# HW_V4_1.net
KiCad netlist of a schematic drawn in Altium Designer
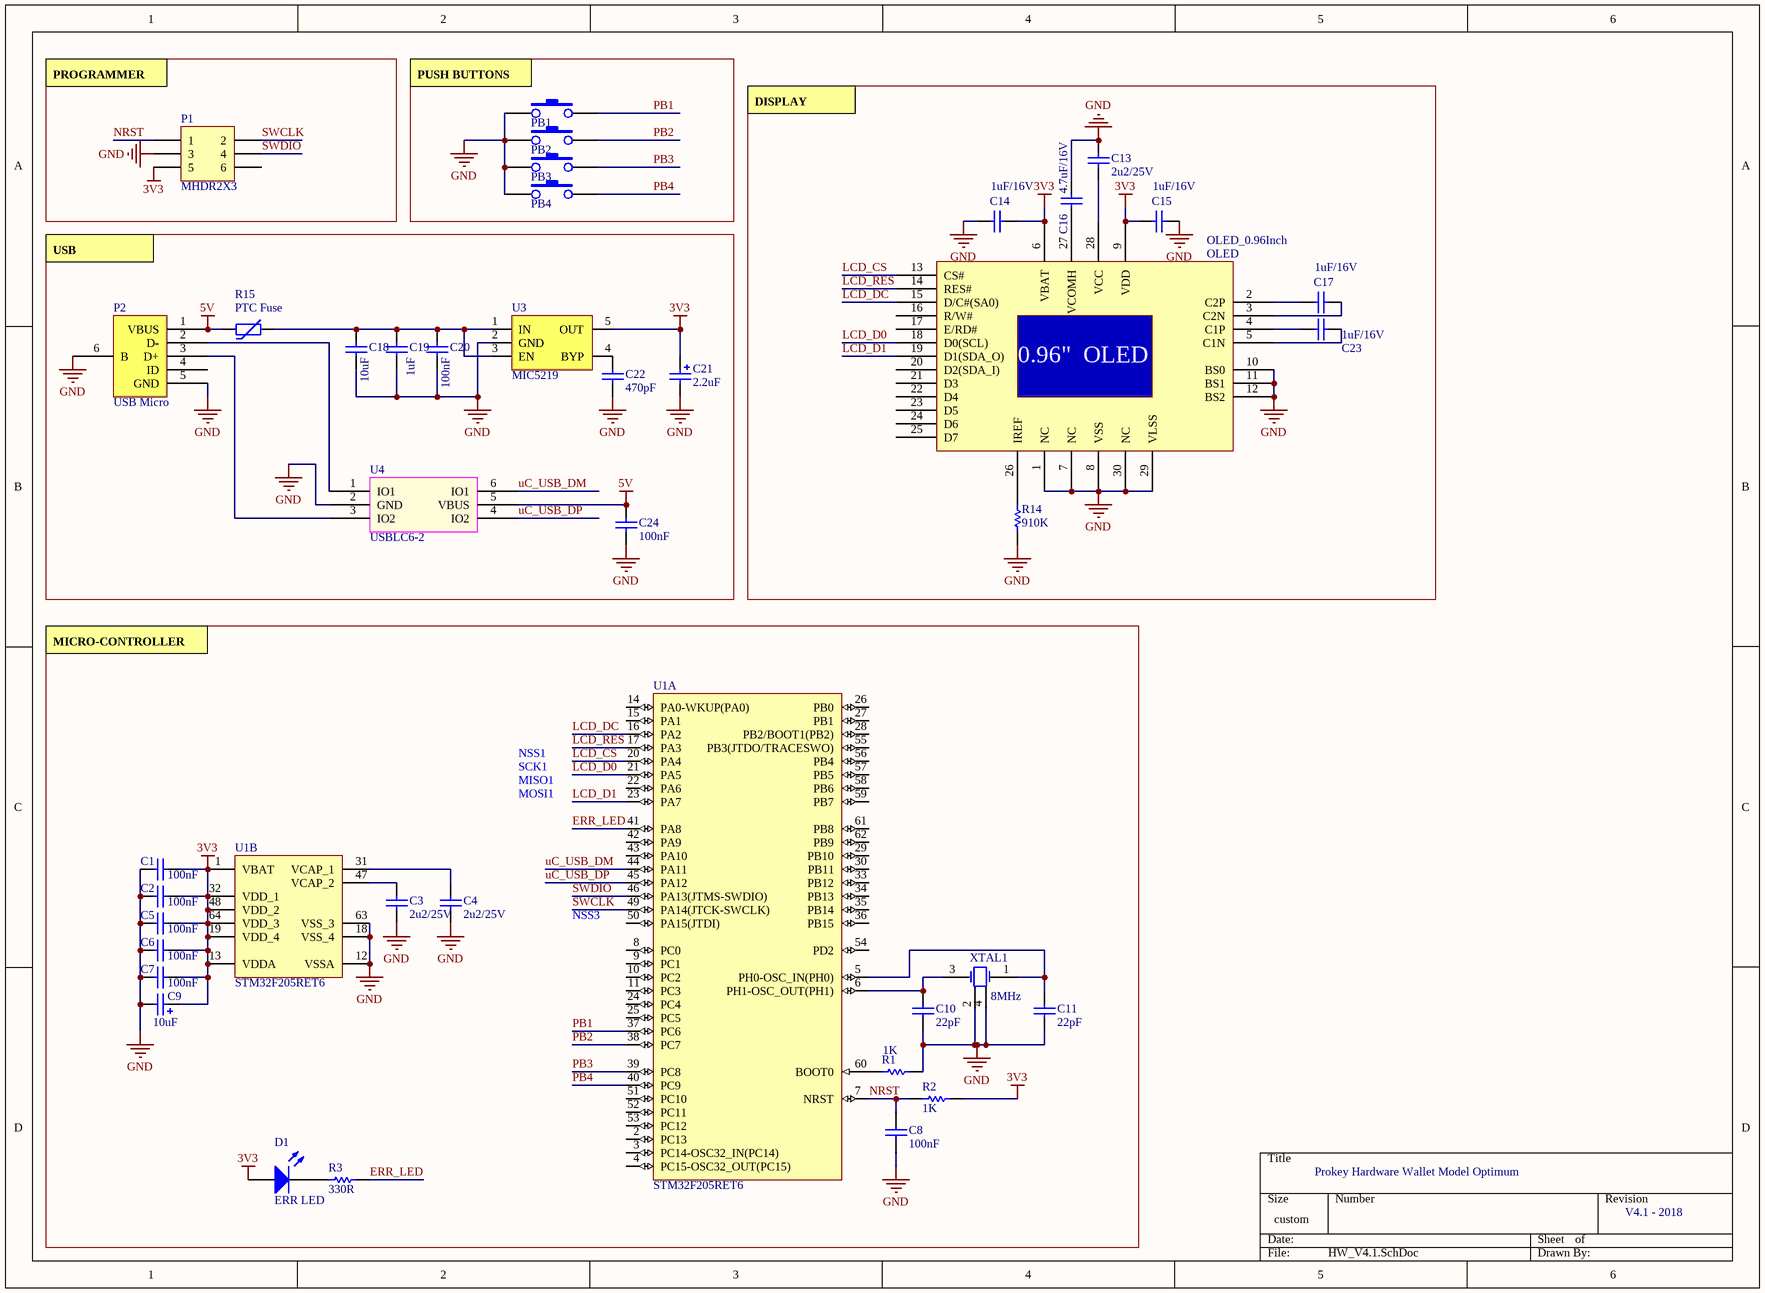
[diagram p0: HW_V4.1.SchDoc]

(export (version "E")
  (design (tool "Eeschema 10.0.6"))
  (components
    (comp (ref "C1")
      (value "100nF")
      (footprint "0603")
      (description "Capacitor")
      (libsource (lib "NSA LIBRARY") (part "CAP"))
    )
    (comp (ref "C2")
      (value "100nF")
      (footprint "0603")
      (description "Capacitor")
      (libsource (lib "NSA LIBRARY") (part "CAP"))
    )
    (comp (ref "C3")
      (value "2u2/25V")
      (footprint "0805")
      (description "Capacitor (Semiconductor SIM Model)")
      (fields (field (name "PUBLISHER") "Altium Limited"))
      (libsource (lib "NSAJ") (part "Cap Semi"))
    )
    (comp (ref "C4")
      (value "2u2/25V")
      (footprint "0805")
      (description "Capacitor (Semiconductor SIM Model)")
      (fields (field (name "PUBLISHER") "Altium Limited"))
      (libsource (lib "NSAJ") (part "Cap Semi"))
    )
    (comp (ref "C5")
      (value "100nF")
      (footprint "0603")
      (description "Capacitor")
      (libsource (lib "NSA LIBRARY") (part "CAP"))
    )
    (comp (ref "C6")
      (value "100nF")
      (footprint "0603")
      (description "Capacitor")
      (libsource (lib "NSA LIBRARY") (part "CAP"))
    )
    (comp (ref "C7")
      (value "100nF")
      (footprint "0603")
      (description "Capacitor")
      (libsource (lib "NSA LIBRARY") (part "CAP"))
    )
    (comp (ref "C8")
      (value "100nF")
      (footprint "0603")
      (description "Capacitor")
      (libsource (lib "NSA LIBRARY") (part "CAP"))
    )
    (comp (ref "C9")
      (value "10uF")
      (footprint "3216P")
      (description "Polarized Capacitor (Surface Mount)")
      (fields (field (name "PUBLISHER") "Altium Limited"))
      (libsource (lib "NSAJ") (part "Cap Pol3"))
    )
    (comp (ref "C10")
      (value "22pF")
      (footprint "0603")
      (description "Capacitor")
      (libsource (lib "NSA LIBRARY") (part "CAP"))
    )
    (comp (ref "C11")
      (value "22pF")
      (footprint "0603")
      (description "Capacitor")
      (libsource (lib "NSA LIBRARY") (part "CAP"))
    )
    (comp (ref "C13")
      (value "2u2/25V")
      (footprint "0805")
      (description "Capacitor (Semiconductor SIM Model)")
      (fields (field (name "PUBLISHER") "Altium Limited"))
      (libsource (lib "NSAJ") (part "Cap Semi"))
    )
    (comp (ref "C14")
      (value "1uF/16V")
      (footprint "0805")
      (description "Capacitor (Semiconductor SIM Model)")
      (fields (field (name "PUBLISHER") "Altium Limited"))
      (libsource (lib "NSAJ") (part "Cap Semi"))
    )
    (comp (ref "C15")
      (value "1uF/16V")
      (footprint "0805")
      (description "Capacitor (Semiconductor SIM Model)")
      (fields (field (name "PUBLISHER") "Altium Limited"))
      (libsource (lib "NSAJ") (part "Cap Semi"))
    )
    (comp (ref "C16")
      (value "4.7uF/16V")
      (footprint "0805")
      (description "Capacitor (Semiconductor SIM Model)")
      (fields (field (name "PUBLISHER") "Altium Limited"))
      (libsource (lib "NSAJ") (part "Cap Semi"))
    )
    (comp (ref "C17")
      (value "1uF/16V")
      (footprint "0805")
      (description "Capacitor (Semiconductor SIM Model)")
      (fields (field (name "PUBLISHER") "Altium Limited"))
      (libsource (lib "NSAJ") (part "Cap Semi"))
    )
    (comp (ref "C18")
      (value "10uF")
      (footprint "0805")
      (description "Capacitor (Semiconductor SIM Model)")
      (fields (field (name "PUBLISHER") "Altium Limited"))
      (libsource (lib "NSAJ") (part "Cap Semi"))
    )
    (comp (ref "C19")
      (value "1uF")
      (footprint "0805")
      (description "Capacitor (Semiconductor SIM Model)")
      (fields (field (name "PUBLISHER") "Altium Limited"))
      (libsource (lib "NSAJ") (part "Cap Semi"))
    )
    (comp (ref "C20")
      (value "100nF")
      (footprint "0603")
      (description "Capacitor (Semiconductor SIM Model)")
      (fields (field (name "PUBLISHER") "Altium Limited"))
      (libsource (lib "NSAJ") (part "Cap Semi"))
    )
    (comp (ref "C21")
      (value "2.2uF")
      (footprint "3216P")
      (description "Polarized Capacitor (Surface Mount)")
      (fields (field (name "PUBLISHER") "Altium Limited"))
      (libsource (lib "NSAJ") (part "Cap Pol3"))
    )
    (comp (ref "C22")
      (value "470pF")
      (footprint "0603")
      (description "Capacitor")
      (libsource (lib "NSA LIBRARY") (part "CAP"))
    )
    (comp (ref "C23")
      (value "1uF/16V")
      (footprint "0805")
      (description "Capacitor (Semiconductor SIM Model)")
      (fields (field (name "PUBLISHER") "Altium Limited"))
      (libsource (lib "NSAJ") (part "Cap Semi"))
    )
    (comp (ref "C24")
      (value "100nF")
      (footprint "0603")
      (description "Capacitor (Semiconductor SIM Model)")
      (fields (field (name "PUBLISHER") "Altium Limited"))
      (libsource (lib "NSAJ") (part "Cap Semi"))
    )
    (comp (ref "D1")
      (value "ERR LED")
      (footprint "d805")
      (description "Typical BLUE SiC LED")
      (fields (field (name "PUBLISHER") "Altium Limited"))
      (libsource (lib "NSA LIBRARY") (part "LED SMD"))
    )
    (comp (ref "OLED")
      (value "OLED_0.96Inch")
      (footprint "OLED_0.96")
      (libsource (lib "HW") (part "OLED_0.96"))
    )
    (comp (ref "P1")
      (value "MHDR2X3")
      (footprint "MHDR2X3")
      (description "Header, 3-Pin, Dual row")
      (fields (field (name "PUBLISHER") "Altium Limited"))
      (libsource (lib "Miscellaneous Connectors") (part "MHDR2X3"))
    )
    (comp (ref "P2") (value "USB Micro") (footprint "USB_MICRO") (libsource (lib "HW") (part "USB Micro")))
    (comp (ref "PB1")
      (value "PUSH BUTTON")
      (footprint "TACTIC_SW_3.7_3.7_0.35")
      (libsource (lib "HW") (part "PUSH BUTTON"))
    )
    (comp (ref "PB2")
      (value "PUSH BUTTON")
      (footprint "TACTIC_SW_3.7_3.7_0.35")
      (libsource (lib "HW") (part "PUSH BUTTON"))
    )
    (comp (ref "PB3")
      (value "PUSH BUTTON")
      (footprint "TACTIC_SW_3.7_3.7_0.35")
      (libsource (lib "HW") (part "PUSH BUTTON"))
    )
    (comp (ref "PB4")
      (value "PUSH BUTTON")
      (footprint "TACTIC_SW_3.7_3.7_0.35")
      (libsource (lib "HW") (part "PUSH BUTTON"))
    )
    (comp (ref "R1")
      (value "1K")
      (footprint "0603")
      (description "Resisor")
      (libsource (lib "NSA LIBRARY") (part "RES"))
    )
    (comp (ref "R2")
      (value "1K")
      (footprint "0603")
      (description "Resisor")
      (libsource (lib "NSA LIBRARY") (part "RES"))
    )
    (comp (ref "R3")
      (value "330R")
      (footprint "0603")
      (description "Semiconductor Resistor")
      (libsource (lib "NSAJ") (part "Res Semi"))
    )
    (comp (ref "R14")
      (value "910K")
      (footprint "0603")
      (description "Semiconductor Resistor")
      (libsource (lib "NSAJ") (part "Res Semi"))
    )
    (comp (ref "R15")
      (value "PTC Fuse")
      (footprint "NTC 0805/2012")
      (description "SMT Resistor")
      (libsource (lib "Passives") (part "Thermistor"))
    )
    (comp (ref "U1")
      (value "STM32F205RET6")
      (footprint "STM-LQFP64_N")
      (libsource (lib "STMicroelectronics STM32 F2") (part "STM32F205RET6"))
    )
    (comp (ref "U3") (value "MIC5219") (footprint "SOT-23-5") (libsource (lib "HW") (part "MIC5219-3.3BM5")))
    (comp (ref "U4") (value "USBLC6-2") (footprint "SOT-666") (libsource (lib "HW") (part "USBLC6-2")))
    (comp (ref "XTAL1")
      (value "8MHz")
      (footprint "XTAL_XYC")
      (libsource (lib "NSA LIBRARY") (part "XTAL_XYC"))
    )
  )
  (nets
    (net (code "1") (name "/ERR_LED") (class "Default")
      (node (ref "R3") (pin "2") (pinfunction "2_2") (pintype "passive"))
      (node (ref "U1") (pin "41") (pinfunction "PA8_41") (pintype "bidirectional"))
    )
    (net (code "2") (name "/LCD_CS") (class "Default")
      (node (ref "OLED") (pin "13") (pinfunction "CS#_13") (pintype "passive"))
      (node (ref "U1") (pin "20") (pinfunction "PA4_20") (pintype "bidirectional"))
    )
    (net (code "3") (name "/LCD_D0") (class "Default")
      (node (ref "OLED") (pin "18") (pinfunction "D0(SCL)_18") (pintype "passive"))
      (node (ref "U1") (pin "21") (pinfunction "PA5_21") (pintype "bidirectional"))
    )
    (net (code "4") (name "/LCD_D1") (class "Default")
      (node (ref "OLED") (pin "19") (pinfunction "D1(SDA_O)_19") (pintype "passive"))
      (node (ref "U1") (pin "23") (pinfunction "PA7_23") (pintype "bidirectional"))
    )
    (net (code "5") (name "/LCD_DC") (class "Default")
      (node (ref "OLED") (pin "15") (pinfunction "D/C#(SA0)_15") (pintype "passive"))
      (node (ref "U1") (pin "16") (pinfunction "PA2_16") (pintype "bidirectional"))
    )
    (net (code "6") (name "/LCD_RES") (class "Default")
      (node (ref "OLED") (pin "14") (pinfunction "RES#_14") (pintype "passive"))
      (node (ref "U1") (pin "17") (pinfunction "PA3_17") (pintype "bidirectional"))
    )
    (net (code "7") (name "/NRST") (class "Default")
      (node (ref "C8") (pin "1") (pinfunction "1_1") (pintype "passive"))
      (node (ref "P1") (pin "1") (pinfunction "1_1") (pintype "passive"))
      (node (ref "R2") (pin "1") (pinfunction "1_1") (pintype "passive"))
      (node (ref "U1") (pin "7") (pinfunction "NRST_7") (pintype "bidirectional"))
    )
    (net (code "8") (name "/PB1") (class "Default")
      (node (ref "PB1") (pin "2") (pinfunction "2_2") (pintype "passive"))
      (node (ref "U1") (pin "37") (pinfunction "PC6_37") (pintype "bidirectional"))
    )
    (net (code "9") (name "/PB2") (class "Default")
      (node (ref "PB2") (pin "2") (pinfunction "2_2") (pintype "passive"))
      (node (ref "U1") (pin "38") (pinfunction "PC7_38") (pintype "bidirectional"))
    )
    (net (code "10") (name "/PB3") (class "Default")
      (node (ref "PB3") (pin "2") (pinfunction "2_2") (pintype "passive"))
      (node (ref "U1") (pin "39") (pinfunction "PC8_39") (pintype "bidirectional"))
    )
    (net (code "11") (name "/PB4") (class "Default")
      (node (ref "PB4") (pin "2") (pinfunction "2_2") (pintype "passive"))
      (node (ref "U1") (pin "40") (pinfunction "PC9_40") (pintype "bidirectional"))
    )
    (net (code "12") (name "/SWCLK") (class "Default")
      (node (ref "P1") (pin "2") (pinfunction "2_2") (pintype "passive"))
      (node (ref "U1") (pin "49") (pinfunction "PA14(JTCK-SWCLK)_49") (pintype "bidirectional"))
    )
    (net (code "13") (name "/SWDIO") (class "Default")
      (node (ref "P1") (pin "4") (pinfunction "4_4") (pintype "passive"))
      (node (ref "U1") (pin "46") (pinfunction "PA13(JTMS-SWDIO)_46") (pintype "bidirectional"))
    )
    (net (code "14") (name "/uC_USB_DM") (class "Default")
      (node (ref "U1") (pin "44") (pinfunction "PA11_44") (pintype "bidirectional"))
      (node (ref "U4") (pin "6") (pinfunction "IO1_6") (pintype "power_in"))
    )
    (net (code "15") (name "/uC_USB_DP") (class "Default")
      (node (ref "U1") (pin "45") (pinfunction "PA12_45") (pintype "bidirectional"))
      (node (ref "U4") (pin "4") (pinfunction "IO2_4") (pintype "power_in"))
    )
    (net (code "16") (name "3V3") (class "Default")
      (node (ref "C1") (pin "2") (pinfunction "2_2") (pintype "passive"))
      (node (ref "C14") (pin "2") (pinfunction "2_2") (pintype "passive"))
      (node (ref "C15") (pin "1") (pinfunction "1_1") (pintype "passive"))
      (node (ref "C2") (pin "2") (pinfunction "2_2") (pintype "passive"))
      (node (ref "C21") (pin "1") (pinfunction "1_1") (pintype "passive"))
      (node (ref "C5") (pin "2") (pinfunction "2_2") (pintype "passive"))
      (node (ref "C6") (pin "2") (pinfunction "2_2") (pintype "passive"))
      (node (ref "C7") (pin "2") (pinfunction "2_2") (pintype "passive"))
      (node (ref "C9") (pin "1") (pinfunction "1_1") (pintype "passive"))
      (node (ref "D1") (pin "1") (pinfunction "A_1") (pintype "passive"))
      (node (ref "OLED") (pin "6") (pinfunction "VBAT_6") (pintype "passive"))
      (node (ref "OLED") (pin "9") (pinfunction "VDD_9") (pintype "passive"))
      (node (ref "P1") (pin "5") (pinfunction "5_5") (pintype "passive"))
      (node (ref "R2") (pin "2") (pinfunction "2_2") (pintype "passive"))
      (node (ref "U1") (pin "1") (pinfunction "VBAT_1") (pintype "power_in"))
      (node (ref "U1") (pin "13") (pinfunction "VDDA_13") (pintype "power_in"))
      (node (ref "U1") (pin "19") (pinfunction "VDD_4_19") (pintype "power_in"))
      (node (ref "U1") (pin "32") (pinfunction "VDD_1_32") (pintype "power_in"))
      (node (ref "U1") (pin "48") (pinfunction "VDD_2_48") (pintype "power_in"))
      (node (ref "U1") (pin "64") (pinfunction "VDD_3_64") (pintype "power_in"))
      (node (ref "U3") (pin "5") (pinfunction "OUT_5") (pintype "passive"))
    )
    (net (code "17") (name "5V") (class "Default")
      (node (ref "C24") (pin "1") (pinfunction "1_1") (pintype "passive"))
      (node (ref "P2") (pin "1") (pinfunction "VBUS_1") (pintype "passive"))
      (node (ref "R15") (pin "1") (pinfunction "1_1") (pintype "passive"))
      (node (ref "U4") (pin "5") (pinfunction "VBUS_5") (pintype "power_in"))
    )
    (net (code "18") (name "GND") (class "Default")
      (node (ref "C1") (pin "1") (pinfunction "1_1") (pintype "passive"))
      (node (ref "C10") (pin "1") (pinfunction "1_1") (pintype "passive"))
      (node (ref "C11") (pin "1") (pinfunction "1_1") (pintype "passive"))
      (node (ref "C13") (pin "2") (pinfunction "2_2") (pintype "passive"))
      (node (ref "C14") (pin "1") (pinfunction "1_1") (pintype "passive"))
      (node (ref "C15") (pin "2") (pinfunction "2_2") (pintype "passive"))
      (node (ref "C16") (pin "2") (pinfunction "2_2") (pintype "passive"))
      (node (ref "C18") (pin "1") (pinfunction "1_1") (pintype "passive"))
      (node (ref "C19") (pin "1") (pinfunction "1_1") (pintype "passive"))
      (node (ref "C2") (pin "1") (pinfunction "1_1") (pintype "passive"))
      (node (ref "C20") (pin "1") (pinfunction "1_1") (pintype "passive"))
      (node (ref "C21") (pin "2") (pinfunction "2_2") (pintype "passive"))
      (node (ref "C22") (pin "1") (pinfunction "1_1") (pintype "passive"))
      (node (ref "C24") (pin "2") (pinfunction "2_2") (pintype "passive"))
      (node (ref "C3") (pin "1") (pinfunction "1_1") (pintype "passive"))
      (node (ref "C4") (pin "1") (pinfunction "1_1") (pintype "passive"))
      (node (ref "C5") (pin "1") (pinfunction "1_1") (pintype "passive"))
      (node (ref "C6") (pin "1") (pinfunction "1_1") (pintype "passive"))
      (node (ref "C7") (pin "1") (pinfunction "1_1") (pintype "passive"))
      (node (ref "C8") (pin "2") (pinfunction "2_2") (pintype "passive"))
      (node (ref "C9") (pin "2") (pinfunction "2_2") (pintype "passive"))
      (node (ref "OLED") (pin "1") (pinfunction "NC_1") (pintype "passive"))
      (node (ref "OLED") (pin "10") (pinfunction "BS0_10") (pintype "passive"))
      (node (ref "OLED") (pin "11") (pinfunction "BS1_11") (pintype "passive"))
      (node (ref "OLED") (pin "12") (pinfunction "BS2_12") (pintype "passive"))
      (node (ref "OLED") (pin "29") (pinfunction "VLSS_29") (pintype "passive"))
      (node (ref "OLED") (pin "30") (pinfunction "NC_30") (pintype "passive"))
      (node (ref "OLED") (pin "7") (pinfunction "NC_7") (pintype "passive"))
      (node (ref "OLED") (pin "8") (pinfunction "VSS_8") (pintype "passive"))
      (node (ref "P1") (pin "3") (pinfunction "3_3") (pintype "passive"))
      (node (ref "P2") (pin "5") (pinfunction "GND_5") (pintype "passive"))
      (node (ref "P2") (pin "6") (pinfunction "B_6") (pintype "passive"))
      (node (ref "PB1") (pin "1") (pinfunction "1_1") (pintype "passive"))
      (node (ref "PB2") (pin "1") (pinfunction "1_1") (pintype "passive"))
      (node (ref "PB3") (pin "1") (pinfunction "1_1") (pintype "passive"))
      (node (ref "PB4") (pin "1") (pinfunction "1_1") (pintype "passive"))
      (node (ref "R1") (pin "2") (pinfunction "2_2") (pintype "passive"))
      (node (ref "R14") (pin "1") (pinfunction "1_1") (pintype "passive"))
      (node (ref "U1") (pin "12") (pinfunction "VSSA_12") (pintype "power_in"))
      (node (ref "U1") (pin "18") (pinfunction "VSS_4_18") (pintype "power_in"))
      (node (ref "U1") (pin "63") (pinfunction "VSS_3_63") (pintype "power_in"))
      (node (ref "U3") (pin "2") (pinfunction "GND_2") (pintype "passive"))
      (node (ref "U4") (pin "2") (pinfunction "GND_2") (pintype "power_in"))
      (node (ref "XTAL1") (pin "2") (pintype "passive"))
      (node (ref "XTAL1") (pin "4") (pintype "passive"))
    )
    (net (code "19") (name "Net-(D1-K)") (class "Default")
      (node (ref "D1") (pin "2") (pinfunction "K_2") (pintype "passive"))
      (node (ref "R3") (pin "1") (pinfunction "1_1") (pintype "passive"))
    )
    (net (code "20") (name "Net-(OLED-C1N)") (class "Default")
      (node (ref "C23") (pin "2") (pinfunction "2_2") (pintype "passive"))
      (node (ref "OLED") (pin "5") (pinfunction "C1N_5") (pintype "passive"))
    )
    (net (code "21") (name "Net-(OLED-C1P)") (class "Default")
      (node (ref "C23") (pin "1") (pinfunction "1_1") (pintype "passive"))
      (node (ref "OLED") (pin "4") (pinfunction "C1P_4") (pintype "passive"))
    )
    (net (code "22") (name "Net-(OLED-C2N)") (class "Default")
      (node (ref "C17") (pin "2") (pinfunction "2_2") (pintype "passive"))
      (node (ref "OLED") (pin "3") (pinfunction "C2N_3") (pintype "passive"))
    )
    (net (code "23") (name "Net-(OLED-C2P)") (class "Default")
      (node (ref "C17") (pin "1") (pinfunction "1_1") (pintype "passive"))
      (node (ref "OLED") (pin "2") (pinfunction "C2P_2") (pintype "passive"))
    )
    (net (code "24") (name "Net-(OLED-IREF)") (class "Default")
      (node (ref "OLED") (pin "26") (pinfunction "IREF_26") (pintype "passive"))
      (node (ref "R14") (pin "2") (pinfunction "2_2") (pintype "passive"))
    )
    (net (code "25") (name "Net-(OLED-VCC)") (class "Default")
      (node (ref "C13") (pin "1") (pinfunction "1_1") (pintype "passive"))
      (node (ref "OLED") (pin "28") (pinfunction "VCC_28") (pintype "passive"))
    )
    (net (code "26") (name "Net-(OLED-VCOMH)") (class "Default")
      (node (ref "C16") (pin "1") (pinfunction "1_1") (pintype "passive"))
      (node (ref "OLED") (pin "27") (pinfunction "VCOMH_27") (pintype "passive"))
    )
    (net (code "27") (name "Net-(P2-D+)") (class "Default")
      (node (ref "P2") (pin "3") (pinfunction "D+_3") (pintype "passive"))
      (node (ref "U4") (pin "3") (pinfunction "IO2_3") (pintype "power_in"))
    )
    (net (code "28") (name "Net-(P2-D-)") (class "Default")
      (node (ref "P2") (pin "2") (pinfunction "D-_2") (pintype "passive"))
      (node (ref "U4") (pin "1") (pinfunction "IO1_1") (pintype "power_in"))
    )
    (net (code "29") (name "Net-(U1A-BOOT0)") (class "Default")
      (node (ref "R1") (pin "1") (pinfunction "1_1") (pintype "passive"))
      (node (ref "U1") (pin "60") (pinfunction "BOOT0_60") (pintype "input"))
    )
    (net (code "30") (name "Net-(U1A-PH0-OSC_IN(PH0))") (class "Default")
      (node (ref "C11") (pin "2") (pinfunction "2_2") (pintype "passive"))
      (node (ref "U1") (pin "5") (pinfunction "PH0-OSC_IN(PH0)_5") (pintype "bidirectional"))
      (node (ref "XTAL1") (pin "1") (pinfunction "OSC1_1") (pintype "passive"))
    )
    (net (code "31") (name "Net-(U1A-PH1-OSC_OUT(PH1))") (class "Default")
      (node (ref "C10") (pin "2") (pinfunction "2_2") (pintype "passive"))
      (node (ref "U1") (pin "6") (pinfunction "PH1-OSC_OUT(PH1)_6") (pintype "bidirectional"))
      (node (ref "XTAL1") (pin "3") (pinfunction "OSC2_3") (pintype "passive"))
    )
    (net (code "32") (name "Net-(U1B-VCAP_1)") (class "Default")
      (node (ref "C4") (pin "2") (pinfunction "2_2") (pintype "passive"))
      (node (ref "U1") (pin "31") (pinfunction "VCAP_1_31") (pintype "power_in"))
    )
    (net (code "33") (name "Net-(U1B-VCAP_2)") (class "Default")
      (node (ref "C3") (pin "2") (pinfunction "2_2") (pintype "passive"))
      (node (ref "U1") (pin "47") (pinfunction "VCAP_2_47") (pintype "power_in"))
    )
    (net (code "34") (name "Net-(U3-BYP)") (class "Default")
      (node (ref "C22") (pin "2") (pinfunction "2_2") (pintype "passive"))
      (node (ref "U3") (pin "4") (pinfunction "BYP_4") (pintype "passive"))
    )
    (net (code "35") (name "Net-(U3-EN)") (class "Default")
      (node (ref "C18") (pin "2") (pinfunction "2_2") (pintype "passive"))
      (node (ref "C19") (pin "2") (pinfunction "2_2") (pintype "passive"))
      (node (ref "C20") (pin "2") (pinfunction "2_2") (pintype "passive"))
      (node (ref "R15") (pin "2") (pinfunction "2_2") (pintype "passive"))
      (node (ref "U3") (pin "1") (pinfunction "IN_1") (pintype "passive"))
      (node (ref "U3") (pin "3") (pinfunction "EN_3") (pintype "passive"))
    )
    (net (code "36") (name "unconnected-(OLED-D2(SDA_I)-Pad20)") (class "Default")
      (node (ref "OLED") (pin "20") (pinfunction "D2(SDA_I)_20") (pintype "passive"))
    )
    (net (code "37") (name "unconnected-(OLED-D3-Pad21)") (class "Default")
      (node (ref "OLED") (pin "21") (pinfunction "D3_21") (pintype "passive"))
    )
    (net (code "38") (name "unconnected-(OLED-D4-Pad22)") (class "Default")
      (node (ref "OLED") (pin "22") (pinfunction "D4_22") (pintype "passive"))
    )
    (net (code "39") (name "unconnected-(OLED-D5-Pad23)") (class "Default")
      (node (ref "OLED") (pin "23") (pinfunction "D5_23") (pintype "passive"))
    )
    (net (code "40") (name "unconnected-(OLED-D6-Pad24)") (class "Default")
      (node (ref "OLED") (pin "24") (pinfunction "D6_24") (pintype "passive"))
    )
    (net (code "41") (name "unconnected-(OLED-D7-Pad25)") (class "Default")
      (node (ref "OLED") (pin "25") (pinfunction "D7_25") (pintype "passive"))
    )
    (net (code "42") (name "unconnected-(OLED-E{slash}RD#-Pad17)") (class "Default")
      (node (ref "OLED") (pin "17") (pinfunction "E/RD#_17") (pintype "passive"))
    )
    (net (code "43") (name "unconnected-(OLED-R{slash}W#-Pad16)") (class "Default")
      (node (ref "OLED") (pin "16") (pinfunction "R/W#_16") (pintype "passive"))
    )
    (net (code "44") (name "unconnected-(P1-Pad6)") (class "Default")
      (node (ref "P1") (pin "6") (pinfunction "6_6") (pintype "passive"))
    )
    (net (code "45") (name "unconnected-(P2-ID-Pad4)") (class "Default")
      (node (ref "P2") (pin "4") (pinfunction "ID_4") (pintype "passive"))
    )
    (net (code "46") (name "unconnected-(U1A-PA0-WKUP(PA0)-Pad14)") (class "Default")
      (node (ref "U1") (pin "14") (pinfunction "PA0-WKUP(PA0)_14") (pintype "bidirectional"))
    )
    (net (code "47") (name "unconnected-(U1A-PA1-Pad15)") (class "Default")
      (node (ref "U1") (pin "15") (pinfunction "PA1_15") (pintype "bidirectional"))
    )
    (net (code "48") (name "unconnected-(U1A-PA6-Pad22)") (class "Default")
      (node (ref "U1") (pin "22") (pinfunction "PA6_22") (pintype "bidirectional"))
    )
    (net (code "49") (name "unconnected-(U1A-PA9-Pad42)") (class "Default")
      (node (ref "U1") (pin "42") (pinfunction "PA9_42") (pintype "bidirectional"))
    )
    (net (code "50") (name "unconnected-(U1A-PA10-Pad43)") (class "Default")
      (node (ref "U1") (pin "43") (pinfunction "PA10_43") (pintype "bidirectional"))
    )
    (net (code "51") (name "unconnected-(U1A-PA15(JTDI)-Pad50)") (class "Default")
      (node (ref "U1") (pin "50") (pinfunction "PA15(JTDI)_50") (pintype "bidirectional"))
    )
    (net (code "52") (name "unconnected-(U1A-PB0-Pad26)") (class "Default")
      (node (ref "U1") (pin "26") (pinfunction "PB0_26") (pintype "bidirectional"))
    )
    (net (code "53") (name "unconnected-(U1A-PB1-Pad27)") (class "Default")
      (node (ref "U1") (pin "27") (pinfunction "PB1_27") (pintype "bidirectional"))
    )
    (net (code "54") (name "unconnected-(U1A-PB2{slash}BOOT1(PB2)-Pad28)") (class "Default")
      (node (ref "U1") (pin "28") (pinfunction "PB2/BOOT1(PB2)_28") (pintype "bidirectional"))
    )
    (net (code "55") (name "unconnected-(U1A-PB3(JTDO{slash}TRACESWO)-Pad55)") (class "Default")
      (node (ref "U1") (pin "55") (pinfunction "PB3(JTDO/TRACESWO)_55") (pintype "bidirectional"))
    )
    (net (code "56") (name "unconnected-(U1A-PB4-Pad56)") (class "Default")
      (node (ref "U1") (pin "56") (pinfunction "PB4_56") (pintype "bidirectional"))
    )
    (net (code "57") (name "unconnected-(U1A-PB5-Pad57)") (class "Default")
      (node (ref "U1") (pin "57") (pinfunction "PB5_57") (pintype "bidirectional"))
    )
    (net (code "58") (name "unconnected-(U1A-PB6-Pad58)") (class "Default")
      (node (ref "U1") (pin "58") (pinfunction "PB6_58") (pintype "bidirectional"))
    )
    (net (code "59") (name "unconnected-(U1A-PB7-Pad59)") (class "Default")
      (node (ref "U1") (pin "59") (pinfunction "PB7_59") (pintype "bidirectional"))
    )
    (net (code "60") (name "unconnected-(U1A-PB8-Pad61)") (class "Default")
      (node (ref "U1") (pin "61") (pinfunction "PB8_61") (pintype "bidirectional"))
    )
    (net (code "61") (name "unconnected-(U1A-PB9-Pad62)") (class "Default")
      (node (ref "U1") (pin "62") (pinfunction "PB9_62") (pintype "bidirectional"))
    )
    (net (code "62") (name "unconnected-(U1A-PB10-Pad29)") (class "Default")
      (node (ref "U1") (pin "29") (pinfunction "PB10_29") (pintype "bidirectional"))
    )
    (net (code "63") (name "unconnected-(U1A-PB11-Pad30)") (class "Default")
      (node (ref "U1") (pin "30") (pinfunction "PB11_30") (pintype "bidirectional"))
    )
    (net (code "64") (name "unconnected-(U1A-PB12-Pad33)") (class "Default")
      (node (ref "U1") (pin "33") (pinfunction "PB12_33") (pintype "bidirectional"))
    )
    (net (code "65") (name "unconnected-(U1A-PB13-Pad34)") (class "Default")
      (node (ref "U1") (pin "34") (pinfunction "PB13_34") (pintype "bidirectional"))
    )
    (net (code "66") (name "unconnected-(U1A-PB14-Pad35)") (class "Default")
      (node (ref "U1") (pin "35") (pinfunction "PB14_35") (pintype "bidirectional"))
    )
    (net (code "67") (name "unconnected-(U1A-PB15-Pad36)") (class "Default")
      (node (ref "U1") (pin "36") (pinfunction "PB15_36") (pintype "bidirectional"))
    )
    (net (code "68") (name "unconnected-(U1A-PC0-Pad8)") (class "Default")
      (node (ref "U1") (pin "8") (pinfunction "PC0_8") (pintype "bidirectional"))
    )
    (net (code "69") (name "unconnected-(U1A-PC1-Pad9)") (class "Default")
      (node (ref "U1") (pin "9") (pinfunction "PC1_9") (pintype "bidirectional"))
    )
    (net (code "70") (name "unconnected-(U1A-PC2-Pad10)") (class "Default")
      (node (ref "U1") (pin "10") (pinfunction "PC2_10") (pintype "bidirectional"))
    )
    (net (code "71") (name "unconnected-(U1A-PC3-Pad11)") (class "Default")
      (node (ref "U1") (pin "11") (pinfunction "PC3_11") (pintype "bidirectional"))
    )
    (net (code "72") (name "unconnected-(U1A-PC4-Pad24)") (class "Default")
      (node (ref "U1") (pin "24") (pinfunction "PC4_24") (pintype "bidirectional"))
    )
    (net (code "73") (name "unconnected-(U1A-PC5-Pad25)") (class "Default")
      (node (ref "U1") (pin "25") (pinfunction "PC5_25") (pintype "bidirectional"))
    )
    (net (code "74") (name "unconnected-(U1A-PC10-Pad51)") (class "Default")
      (node (ref "U1") (pin "51") (pinfunction "PC10_51") (pintype "bidirectional"))
    )
    (net (code "75") (name "unconnected-(U1A-PC11-Pad52)") (class "Default")
      (node (ref "U1") (pin "52") (pinfunction "PC11_52") (pintype "bidirectional"))
    )
    (net (code "76") (name "unconnected-(U1A-PC12-Pad53)") (class "Default")
      (node (ref "U1") (pin "53") (pinfunction "PC12_53") (pintype "bidirectional"))
    )
    (net (code "77") (name "unconnected-(U1A-PC13-Pad2)") (class "Default")
      (node (ref "U1") (pin "2") (pinfunction "PC13_2") (pintype "bidirectional"))
    )
    (net (code "78") (name "unconnected-(U1A-PC14-OSC32_IN(PC14)-Pad3)") (class "Default")
      (node (ref "U1") (pin "3") (pinfunction "PC14-OSC32_IN(PC14)_3") (pintype "bidirectional"))
    )
    (net (code "79") (name "unconnected-(U1A-PC15-OSC32_OUT(PC15)-Pad4)") (class "Default")
      (node (ref "U1") (pin "4") (pinfunction "PC15-OSC32_OUT(PC15)_4") (pintype "bidirectional"))
    )
    (net (code "80") (name "unconnected-(U1A-PD2-Pad54)") (class "Default")
      (node (ref "U1") (pin "54") (pinfunction "PD2_54") (pintype "bidirectional"))
    )
  )
)
